# Main.net
KiCad netlist of a schematic drawn in Altium Designer
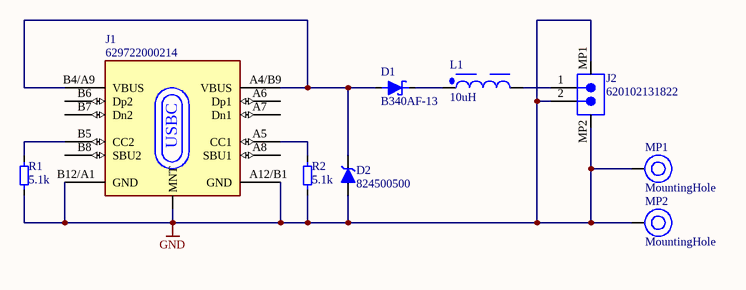
[diagram p0: Main.SchDoc]

(export (version "E")
  (design (tool "Eeschema 10.0.6"))
  (components
    (comp (ref "D1")
      (value "B340AF-13")
      (footprint "DO-214AC_UNI")
      (description "Diode 40 V 3A Surface Mount SMAF")
      (fields (field (name "JLCPCB PART #") "C5310924"))
      (libsource (lib "7c7 Engineering") (part "DIODE-SKY-2"))
    )
    (comp (ref "D2")
      (value "824500500")
      (footprint "DO-214AC_UNI")
      (description "WE-TVSP SMT Power TVS Diode, DO-214AC, 400W, 5VDC, Unidirectional")
      (fields (field (name "MANUFACTURER") "Wurth Elektronik") (field (name "JLCPCB PART #") "C2925443"))
      (libsource (lib "7c7 Engineering") (part "DIODE-ZEN-2"))
    )
    (comp (ref "J1")
      (value "629722000214")
      (footprint "629722000214")
      (description "WR-USB 2.0 Type C, Receptacle, Horizontal, SMT")
      (fields (field (name "JLCPCB PART #") "C2982555") (field (name "MANUFACTURER") "Wurth Elektronik"))
      (libsource (lib "7c7 Engineering") (part "629722000214"))
    )
    (comp (ref "J2")
      (value "620102131822")
      (footprint "620102131822")
      (description "WR-WTB SMT Male Horizontal Shrouded Header, pitch 2mm, 2p")
      (fields (field (name "JLCPCB PART #") "C295747") (field (name "PUBLISHER") "Wurth Elektronik"))
      (libsource (lib "7c7 Engineering") (part "HDR_2P_2MP"))
    )
    (comp (ref "L1")
      (value "78438357100")
      (footprint "WE-MAIA_4030")
      (description "WE-MAIA SMT Power Inductor, size 4030, 10uH, 3.05A, 110mOhm")
      (fields
        (field (name "MANUFACTURER") "Wurth Elektronik")
        (field (name "INDUCTANCE") "10uH")
        (field (name "JLCPCB PART #") "C167879")
      )
      (libsource (lib "7c7 Engineering") (part "784383560068HT"))
    )
    (comp (ref "MP1")
      (value "MountingHole")
      (footprint "PTH-M2D4.1X4.1")
      (libsource (lib "7c7 Engineering") (part "MECH_NO_BOM"))
    )
    (comp (ref "MP2")
      (value "MountingHole")
      (footprint "PTH-M2D4.1X4.1")
      (libsource (lib "7c7 Engineering") (part "MECH_NO_BOM"))
    )
    (comp (ref "R1")
      (value "5.1k")
      (footprint "0603-R-N")
      (description "Chip Resistor, Thick Film, General Purpose, 0603, 100mW, 50V, 5.1 kOhm, +/-1%")
      (fields (field (name "TOLERANCE") "1%") (field (name "JLCPCB PART #") "C144594"))
      (libsource (lib "7c7 Engineering") (part "RES"))
    )
    (comp (ref "R2")
      (value "5.1k")
      (footprint "0603-R-N")
      (description "Chip Resistor, Thick Film, General Purpose, 0603, 100mW, 50V, 5.1 kOhm, +/-1%")
      (fields (field (name "TOLERANCE") "1%") (field (name "JLCPCB PART #") "C144594"))
      (libsource (lib "7c7 Engineering") (part "RES"))
    )
  )
  (nets
    (net (code "1") (name "GND") (class "Default")
      (node (ref "D2") (pin "2") (pinfunction "A_2") (pintype "passive"))
      (node (ref "J1") (pin "A12/B1") (pinfunction "GND_A12/B1") (pintype "passive"))
      (node (ref "J1") (pin "B12/A1") (pinfunction "GND_B12/A1") (pintype "passive"))
      (node (ref "J1") (pin "MNT") (pinfunction "MNT_MNT") (pintype "power_in"))
      (node (ref "J2") (pin "2") (pinfunction "2_2") (pintype "passive"))
      (node (ref "J2") (pin "MP1") (pinfunction "MP1_MP1") (pintype "passive"))
      (node (ref "J2") (pin "MP2") (pinfunction "MP2_MP2") (pintype "passive"))
      (node (ref "MP1") (pin "1") (pinfunction "H1_1") (pintype "passive"))
      (node (ref "MP2") (pin "1") (pinfunction "H1_1") (pintype "passive"))
      (node (ref "R1") (pin "2") (pinfunction "2_2") (pintype "passive"))
      (node (ref "R2") (pin "2") (pinfunction "2_2") (pintype "passive"))
    )
    (net (code "2") (name "Net-(D1-A)") (class "Default")
      (node (ref "D1") (pin "2") (pinfunction "A_2") (pintype "passive"))
      (node (ref "D2") (pin "1") (pinfunction "K_1") (pintype "passive"))
      (node (ref "J1") (pin "A4/B9") (pinfunction "VBUS_A4/B9") (pintype "passive"))
      (node (ref "J1") (pin "B4/A9") (pinfunction "VBUS_B4/A9") (pintype "passive"))
    )
    (net (code "3") (name "Net-(D1-K)") (class "Default")
      (node (ref "D1") (pin "1") (pinfunction "K_1") (pintype "passive"))
      (node (ref "L1") (pin "1") (pinfunction "1_1") (pintype "passive"))
    )
    (net (code "4") (name "Net-(J1-CC1)") (class "Default")
      (node (ref "J1") (pin "A5") (pinfunction "CC1_A5") (pintype "bidirectional"))
      (node (ref "R2") (pin "1") (pinfunction "1_1") (pintype "passive"))
    )
    (net (code "5") (name "Net-(J1-CC2)") (class "Default")
      (node (ref "J1") (pin "B5") (pinfunction "CC2_B5") (pintype "bidirectional"))
      (node (ref "R1") (pin "1") (pinfunction "1_1") (pintype "passive"))
    )
    (net (code "6") (name "Net-(J2-Pad1)") (class "Default")
      (node (ref "J2") (pin "1") (pinfunction "1_1") (pintype "passive"))
      (node (ref "L1") (pin "2") (pinfunction "2_2") (pintype "passive"))
    )
    (net (code "7") (name "unconnected-(J1-Dn1-PadA7)") (class "Default")
      (node (ref "J1") (pin "A7") (pinfunction "Dn1_A7") (pintype "bidirectional"))
    )
    (net (code "8") (name "unconnected-(J1-Dn2-PadB7)") (class "Default")
      (node (ref "J1") (pin "B7") (pinfunction "Dn2_B7") (pintype "bidirectional"))
    )
    (net (code "9") (name "unconnected-(J1-Dp1-PadA6)") (class "Default")
      (node (ref "J1") (pin "A6") (pinfunction "Dp1_A6") (pintype "bidirectional"))
    )
    (net (code "10") (name "unconnected-(J1-Dp2-PadB6)") (class "Default")
      (node (ref "J1") (pin "B6") (pinfunction "Dp2_B6") (pintype "bidirectional"))
    )
    (net (code "11") (name "unconnected-(J1-SBU1-PadA8)") (class "Default")
      (node (ref "J1") (pin "A8") (pinfunction "SBU1_A8") (pintype "bidirectional"))
    )
    (net (code "12") (name "unconnected-(J1-SBU2-PadB8)") (class "Default")
      (node (ref "J1") (pin "B8") (pinfunction "SBU2_B8") (pintype "bidirectional"))
    )
  )
)
